# esp.net
KiCad netlist of a schematic drawn in Altium Designer
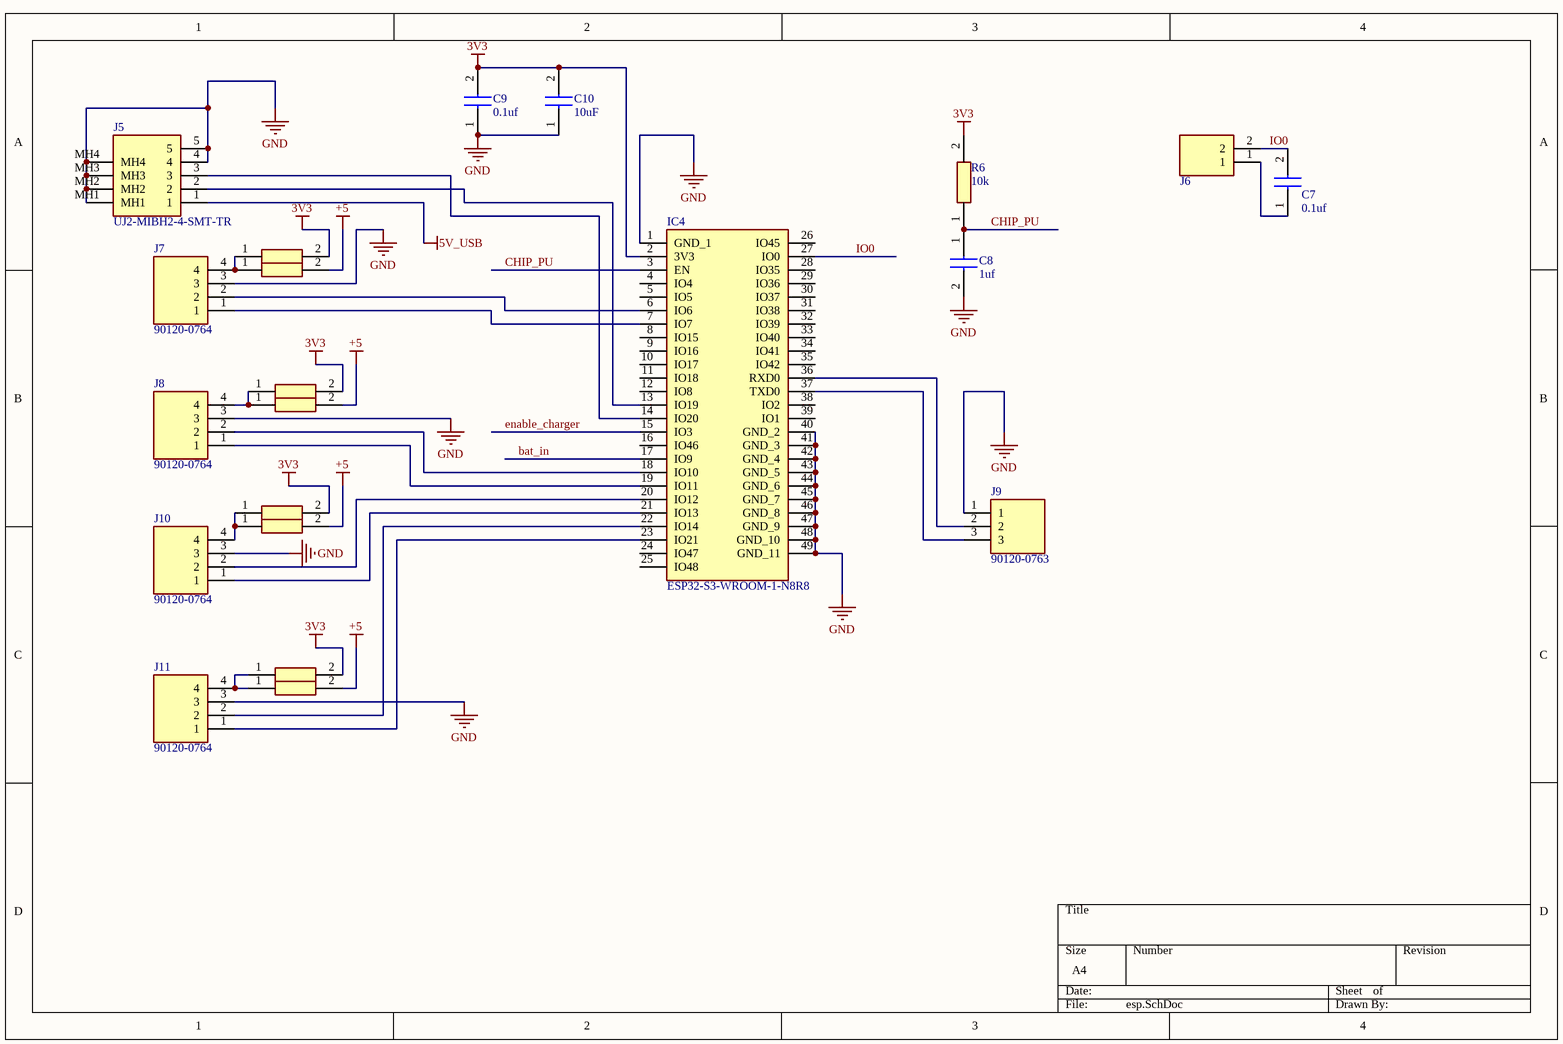
[diagram p0: esp.SchDoc]

(export (version "E")
  (design (tool "Eeschema 10.0.6"))
  (components
    (comp (ref "C7")
      (value "0.1uf")
      (footprint "SamacSys:C0805")
      (description "Capacitor")
      (fields (field (name "MANUFACTURER_PART_NUMBER") "C0805C104J5RACTM"))
      (libsource (lib "*") (part "C0805C104J5RACTM"))
    )
    (comp (ref "C8")
      (value "1uf")
      (footprint "SamacSys:C0805")
      (description "Capacitor")
      (fields (field (name "MANUFACTURER_PART_NUMBER") "C0805C104J5RACTM"))
      (libsource (lib "*") (part "C0805C104J5RACTM"))
    )
    (comp (ref "C9")
      (value "0.1uf")
      (footprint "SamacSys:CAPC2012X145N")
      (description "Capacitor")
      (fields
        (field (name "MANUFACTURER_PART_NUMBER") "VJ0805Y104KXAAT")
        (field (name "MOUSER PART NUMBER") "77-VJ0805Y104KXAAT")
      )
      (libsource (lib "*") (part "VJ0805Y104KXAAT"))
    )
    (comp (ref "C10")
      (value "10uF")
      (footprint "SamacSys:CAPC2114X145N")
      (description "Capacitor")
      (fields
        (field (name "MANUFACTURER_PART_NUMBER") "LMR212BD7106KG-T")
        (field (name "MOUSER PART NUMBER") "963-LMR212BD7106KG-T")
      )
      (libsource (lib "*") (part "LMR212BD7106KG-T"))
    )
    (comp (ref "IC4")
      (value "ESP32-S3-WROOM-1-N8R8")
      (footprint "SamacSys:ESP32S3WROOM1N8R8")
      (description "Integrated Circuit")
      (fields (field (name "MOUSER PART NUMBER") "356-EP32S3WROOM1N8R8"))
      (libsource (lib "*") (part "ESP32-S3-WROOM-1-N8R8"))
    )
    (comp (ref "J5")
      (value "UJ2-MIBH2-4-SMT-TR")
      (footprint "SamacSys:UJ2MIBH24SMTTR")
      (description "Connector")
      (fields (field (name "MOUSER PART NUMBER") "490-UJ2-MIBH2-4-SMT"))
      (libsource (lib "*") (part "UJ2-MIBH2-4-SMT-TR"))
    )
    (comp (ref "J6")
      (value "10129378-902001BLF")
      (footprint "SamacSys:HDRV2W67P0X254_1X2_508X241X843P")
      (description "Connector")
      (fields (field (name "MOUSER PART NUMBER") "649-1012937890201BLF"))
      (libsource (lib "*") (part "10129378-902001BLF"))
    )
    (comp (ref "J7")
      (value "90120-0764")
      (footprint "SamacSys:HDRV4W90P0X254_1X4_994X249X560P")
      (description "Connector")
      (fields (field (name "MOUSER PART NUMBER") "538-90120-0764"))
      (libsource (lib "SamacSys") (part "90120-0764"))
    )
    (comp (ref "J8")
      (value "90120-0764")
      (footprint "SamacSys:HDRV4W90P0X254_1X4_994X249X560P")
      (description "Connector")
      (fields (field (name "MOUSER PART NUMBER") "538-90120-0764"))
      (libsource (lib "SamacSys") (part "90120-0764"))
    )
    (comp (ref "J9")
      (value "90120-0763")
      (footprint "SamacSys:HDRV3W90P0X254_1X3_740X249X560P")
      (description "Connector")
      (fields (field (name "MOUSER PART NUMBER") "538-90120-0763"))
      (libsource (lib "*") (part "90120-0763"))
    )
    (comp (ref "J10")
      (value "90120-0764")
      (footprint "SamacSys:HDRV4W90P0X254_1X4_994X249X560P")
      (description "Connector")
      (fields (field (name "MOUSER PART NUMBER") "538-90120-0764"))
      (libsource (lib "SamacSys") (part "90120-0764"))
    )
    (comp (ref "J11")
      (value "90120-0764")
      (footprint "SamacSys:HDRV4W90P0X254_1X4_994X249X560P")
      (description "Connector")
      (fields (field (name "MOUSER PART NUMBER") "538-90120-0764"))
      (libsource (lib "SamacSys") (part "90120-0764"))
    )
    (comp (ref "R6")
      (value "10k")
      (footprint "SamacSys:RESC2012X65N")
      (description "Resistor")
      (fields
        (field (name "MANUFACTURER_PART_NUMBER") "CPF0805B10K5E1")
        (field (name "MOUSER PART NUMBER") "279-CPF0805B10K5E1")
      )
      (libsource (lib "*") (part "CPF0805B10K5E1"))
    )
    (comp (ref "R7")
      (value "CRCW08050000Z0EB")
      (footprint "SamacSys:RESC2012X50N")
      (description "Resistor")
      (fields (field (name "MOUSER PART NUMBER") "71-CRCW08050000Z0EB"))
      (libsource (lib "*") (part "CRCW08050000Z0EB"))
    )
    (comp (ref "R8")
      (value "CRCW08050000Z0EB")
      (footprint "SamacSys:RESC2012X50N")
      (description "Resistor")
      (fields (field (name "MOUSER PART NUMBER") "71-CRCW08050000Z0EB"))
      (libsource (lib "*") (part "CRCW08050000Z0EB"))
    )
    (comp (ref "R9")
      (value "CRCW08050000Z0EB")
      (footprint "SamacSys:RESC2012X50N")
      (description "Resistor")
      (fields (field (name "MOUSER PART NUMBER") "71-CRCW08050000Z0EB"))
      (libsource (lib "*") (part "CRCW08050000Z0EB"))
    )
    (comp (ref "R10")
      (value "CRCW08050000Z0EB")
      (footprint "SamacSys:RESC2012X50N")
      (description "Resistor")
      (fields (field (name "MOUSER PART NUMBER") "71-CRCW08050000Z0EB"))
      (libsource (lib "*") (part "CRCW08050000Z0EB"))
    )
    (comp (ref "R11")
      (value "CRCW08050000Z0EB")
      (footprint "SamacSys:RESC2012X50N")
      (description "Resistor")
      (fields (field (name "MOUSER PART NUMBER") "71-CRCW08050000Z0EB"))
      (libsource (lib "*") (part "CRCW08050000Z0EB"))
    )
    (comp (ref "R12")
      (value "CRCW08050000Z0EB")
      (footprint "SamacSys:RESC2012X50N")
      (description "Resistor")
      (fields (field (name "MOUSER PART NUMBER") "71-CRCW08050000Z0EB"))
      (libsource (lib "*") (part "CRCW08050000Z0EB"))
    )
    (comp (ref "R13")
      (value "CRCW08050000Z0EB")
      (footprint "SamacSys:RESC2012X50N")
      (description "Resistor")
      (fields (field (name "MOUSER PART NUMBER") "71-CRCW08050000Z0EB"))
      (libsource (lib "*") (part "CRCW08050000Z0EB"))
    )
    (comp (ref "R14")
      (value "CRCW08050000Z0EB")
      (footprint "SamacSys:RESC2012X50N")
      (description "Resistor")
      (fields (field (name "MOUSER PART NUMBER") "71-CRCW08050000Z0EB"))
      (libsource (lib "*") (part "CRCW08050000Z0EB"))
    )
  )
  (nets
    (net (code "1") (name "+5") (class "Default")
      (node (ref "R10") (pin "2") (pinfunction "2_2") (pintype "passive"))
      (node (ref "R12") (pin "2") (pinfunction "2_2") (pintype "passive"))
      (node (ref "R14") (pin "2") (pinfunction "2_2") (pintype "passive"))
      (node (ref "R8") (pin "2") (pinfunction "2_2") (pintype "passive"))
    )
    (net (code "2") (name "/CHIP_PU") (class "Default")
      (node (ref "C8") (pin "1") (pinfunction "1_1") (pintype "passive"))
      (node (ref "IC4") (pin "3") (pinfunction "EN_3") (pintype "passive"))
      (node (ref "R6") (pin "1") (pinfunction "1_1") (pintype "passive"))
    )
    (net (code "3") (name "/IO0") (class "Default")
      (node (ref "C7") (pin "2") (pinfunction "2_2") (pintype "passive"))
      (node (ref "IC4") (pin "27") (pinfunction "IO0_27") (pintype "passive"))
      (node (ref "J6") (pin "2") (pinfunction "2_2") (pintype "passive"))
    )
    (net (code "4") (name "/bat_in") (class "Default")
      (node (ref "IC4") (pin "17") (pinfunction "IO9_17") (pintype "passive"))
    )
    (net (code "5") (name "/enable_charger") (class "Default")
      (node (ref "IC4") (pin "15") (pinfunction "IO3_15") (pintype "passive"))
    )
    (net (code "6") (name "3V3") (class "Default")
      (node (ref "C10") (pin "2") (pinfunction "2_2") (pintype "passive"))
      (node (ref "C9") (pin "2") (pinfunction "2_2") (pintype "passive"))
      (node (ref "IC4") (pin "2") (pinfunction "3V3_2") (pintype "passive"))
      (node (ref "R11") (pin "2") (pinfunction "2_2") (pintype "passive"))
      (node (ref "R13") (pin "2") (pinfunction "2_2") (pintype "passive"))
      (node (ref "R6") (pin "2") (pinfunction "2_2") (pintype "passive"))
      (node (ref "R7") (pin "2") (pinfunction "2_2") (pintype "passive"))
      (node (ref "R9") (pin "2") (pinfunction "2_2") (pintype "passive"))
    )
    (net (code "7") (name "5V_USB") (class "Default")
      (node (ref "J5") (pin "1") (pinfunction "1_1") (pintype "passive"))
    )
    (net (code "8") (name "GND") (class "Default")
      (node (ref "C10") (pin "1") (pinfunction "1_1") (pintype "passive"))
      (node (ref "C8") (pin "2") (pinfunction "2_2") (pintype "passive"))
      (node (ref "C9") (pin "1") (pinfunction "1_1") (pintype "passive"))
      (node (ref "IC4") (pin "1") (pinfunction "GND_1_1") (pintype "passive"))
      (node (ref "IC4") (pin "40") (pinfunction "GND_2_40") (pintype "passive"))
      (node (ref "IC4") (pin "41") (pinfunction "GND_3_41") (pintype "passive"))
      (node (ref "IC4") (pin "42") (pinfunction "GND_4_42") (pintype "passive"))
      (node (ref "IC4") (pin "43") (pinfunction "GND_5_43") (pintype "passive"))
      (node (ref "IC4") (pin "44") (pinfunction "GND_6_44") (pintype "passive"))
      (node (ref "IC4") (pin "45") (pinfunction "GND_7_45") (pintype "passive"))
      (node (ref "IC4") (pin "46") (pinfunction "GND_8_46") (pintype "passive"))
      (node (ref "IC4") (pin "47") (pinfunction "GND_9_47") (pintype "passive"))
      (node (ref "IC4") (pin "48") (pinfunction "GND_10_48") (pintype "passive"))
      (node (ref "IC4") (pin "49") (pinfunction "GND_11_49") (pintype "passive"))
      (node (ref "J10") (pin "3") (pinfunction "3_3") (pintype "passive"))
      (node (ref "J11") (pin "3") (pinfunction "3_3") (pintype "passive"))
      (node (ref "J5") (pin "4") (pinfunction "4_4") (pintype "passive"))
      (node (ref "J5") (pin "5") (pinfunction "5_5") (pintype "passive"))
      (node (ref "J5") (pin "MH1") (pinfunction "MH1_MH1") (pintype "passive"))
      (node (ref "J5") (pin "MH2") (pinfunction "MH2_MH2") (pintype "passive"))
      (node (ref "J5") (pin "MH3") (pinfunction "MH3_MH3") (pintype "passive"))
      (node (ref "J5") (pin "MH4") (pinfunction "MH4_MH4") (pintype "passive"))
      (node (ref "J7") (pin "3") (pinfunction "3_3") (pintype "passive"))
      (node (ref "J8") (pin "3") (pinfunction "3_3") (pintype "passive"))
      (node (ref "J9") (pin "1") (pinfunction "1_1") (pintype "passive"))
    )
    (net (code "9") (name "Net-(C7-Pad1)") (class "Default")
      (node (ref "C7") (pin "1") (pinfunction "1_1") (pintype "passive"))
      (node (ref "J6") (pin "1") (pinfunction "1_1") (pintype "passive"))
    )
    (net (code "10") (name "Net-(IC4-IO6)") (class "Default")
      (node (ref "IC4") (pin "6") (pinfunction "IO6_6") (pintype "passive"))
      (node (ref "J7") (pin "2") (pinfunction "2_2") (pintype "passive"))
    )
    (net (code "11") (name "Net-(IC4-IO7)") (class "Default")
      (node (ref "IC4") (pin "7") (pinfunction "IO7_7") (pintype "passive"))
      (node (ref "J7") (pin "1") (pinfunction "1_1") (pintype "passive"))
    )
    (net (code "12") (name "Net-(IC4-IO10)") (class "Default")
      (node (ref "IC4") (pin "18") (pinfunction "IO10_18") (pintype "passive"))
      (node (ref "J8") (pin "2") (pinfunction "2_2") (pintype "passive"))
    )
    (net (code "13") (name "Net-(IC4-IO11)") (class "Default")
      (node (ref "IC4") (pin "19") (pinfunction "IO11_19") (pintype "passive"))
      (node (ref "J8") (pin "1") (pinfunction "1_1") (pintype "passive"))
    )
    (net (code "14") (name "Net-(IC4-IO12)") (class "Default")
      (node (ref "IC4") (pin "20") (pinfunction "IO12_20") (pintype "passive"))
      (node (ref "J10") (pin "2") (pinfunction "2_2") (pintype "passive"))
    )
    (net (code "15") (name "Net-(IC4-IO13)") (class "Default")
      (node (ref "IC4") (pin "21") (pinfunction "IO13_21") (pintype "passive"))
      (node (ref "J10") (pin "1") (pinfunction "1_1") (pintype "passive"))
    )
    (net (code "16") (name "Net-(IC4-IO14)") (class "Default")
      (node (ref "IC4") (pin "22") (pinfunction "IO14_22") (pintype "passive"))
      (node (ref "J11") (pin "2") (pinfunction "2_2") (pintype "passive"))
    )
    (net (code "17") (name "Net-(IC4-IO19)") (class "Default")
      (node (ref "IC4") (pin "13") (pinfunction "IO19_13") (pintype "passive"))
      (node (ref "J5") (pin "2") (pinfunction "2_2") (pintype "passive"))
    )
    (net (code "18") (name "Net-(IC4-IO20)") (class "Default")
      (node (ref "IC4") (pin "14") (pinfunction "IO20_14") (pintype "passive"))
      (node (ref "J5") (pin "3") (pinfunction "3_3") (pintype "passive"))
    )
    (net (code "19") (name "Net-(IC4-IO21)") (class "Default")
      (node (ref "IC4") (pin "23") (pinfunction "IO21_23") (pintype "passive"))
      (node (ref "J11") (pin "1") (pinfunction "1_1") (pintype "passive"))
    )
    (net (code "20") (name "Net-(IC4-RXD0)") (class "Default")
      (node (ref "IC4") (pin "36") (pinfunction "RXD0_36") (pintype "passive"))
      (node (ref "J9") (pin "2") (pinfunction "2_2") (pintype "passive"))
    )
    (net (code "21") (name "Net-(IC4-TXD0)") (class "Default")
      (node (ref "IC4") (pin "37") (pinfunction "TXD0_37") (pintype "passive"))
      (node (ref "J9") (pin "3") (pinfunction "3_3") (pintype "passive"))
    )
    (net (code "22") (name "Net-(J7-Pad4)") (class "Default")
      (node (ref "J7") (pin "4") (pinfunction "4_4") (pintype "passive"))
      (node (ref "R7") (pin "1") (pinfunction "1_1") (pintype "passive"))
      (node (ref "R8") (pin "1") (pinfunction "1_1") (pintype "passive"))
    )
    (net (code "23") (name "Net-(J8-Pad4)") (class "Default")
      (node (ref "J8") (pin "4") (pinfunction "4_4") (pintype "passive"))
      (node (ref "R10") (pin "1") (pinfunction "1_1") (pintype "passive"))
      (node (ref "R9") (pin "1") (pinfunction "1_1") (pintype "passive"))
    )
    (net (code "24") (name "Net-(J10-Pad4)") (class "Default")
      (node (ref "J10") (pin "4") (pinfunction "4_4") (pintype "passive"))
      (node (ref "R11") (pin "1") (pinfunction "1_1") (pintype "passive"))
      (node (ref "R12") (pin "1") (pinfunction "1_1") (pintype "passive"))
    )
    (net (code "25") (name "Net-(J11-Pad4)") (class "Default")
      (node (ref "J11") (pin "4") (pinfunction "4_4") (pintype "passive"))
      (node (ref "R13") (pin "1") (pinfunction "1_1") (pintype "passive"))
      (node (ref "R14") (pin "1") (pinfunction "1_1") (pintype "passive"))
    )
    (net (code "26") (name "unconnected-(IC4-IO1-Pad39)") (class "Default")
      (node (ref "IC4") (pin "39") (pinfunction "IO1_39") (pintype "passive"))
    )
    (net (code "27") (name "unconnected-(IC4-IO2-Pad38)") (class "Default")
      (node (ref "IC4") (pin "38") (pinfunction "IO2_38") (pintype "passive"))
    )
    (net (code "28") (name "unconnected-(IC4-IO4-Pad4)") (class "Default")
      (node (ref "IC4") (pin "4") (pinfunction "IO4_4") (pintype "passive"))
    )
    (net (code "29") (name "unconnected-(IC4-IO5-Pad5)") (class "Default")
      (node (ref "IC4") (pin "5") (pinfunction "IO5_5") (pintype "passive"))
    )
    (net (code "30") (name "unconnected-(IC4-IO8-Pad12)") (class "Default")
      (node (ref "IC4") (pin "12") (pinfunction "IO8_12") (pintype "passive"))
    )
    (net (code "31") (name "unconnected-(IC4-IO15-Pad8)") (class "Default")
      (node (ref "IC4") (pin "8") (pinfunction "IO15_8") (pintype "passive"))
    )
    (net (code "32") (name "unconnected-(IC4-IO16-Pad9)") (class "Default")
      (node (ref "IC4") (pin "9") (pinfunction "IO16_9") (pintype "passive"))
    )
    (net (code "33") (name "unconnected-(IC4-IO17-Pad10)") (class "Default")
      (node (ref "IC4") (pin "10") (pinfunction "IO17_10") (pintype "passive"))
    )
    (net (code "34") (name "unconnected-(IC4-IO18-Pad11)") (class "Default")
      (node (ref "IC4") (pin "11") (pinfunction "IO18_11") (pintype "passive"))
    )
    (net (code "35") (name "unconnected-(IC4-IO35-Pad28)") (class "Default")
      (node (ref "IC4") (pin "28") (pinfunction "IO35_28") (pintype "passive"))
    )
    (net (code "36") (name "unconnected-(IC4-IO36-Pad29)") (class "Default")
      (node (ref "IC4") (pin "29") (pinfunction "IO36_29") (pintype "passive"))
    )
    (net (code "37") (name "unconnected-(IC4-IO37-Pad30)") (class "Default")
      (node (ref "IC4") (pin "30") (pinfunction "IO37_30") (pintype "passive"))
    )
    (net (code "38") (name "unconnected-(IC4-IO38-Pad31)") (class "Default")
      (node (ref "IC4") (pin "31") (pinfunction "IO38_31") (pintype "passive"))
    )
    (net (code "39") (name "unconnected-(IC4-IO39-Pad32)") (class "Default")
      (node (ref "IC4") (pin "32") (pinfunction "IO39_32") (pintype "passive"))
    )
    (net (code "40") (name "unconnected-(IC4-IO40-Pad33)") (class "Default")
      (node (ref "IC4") (pin "33") (pinfunction "IO40_33") (pintype "passive"))
    )
    (net (code "41") (name "unconnected-(IC4-IO41-Pad34)") (class "Default")
      (node (ref "IC4") (pin "34") (pinfunction "IO41_34") (pintype "passive"))
    )
    (net (code "42") (name "unconnected-(IC4-IO42-Pad35)") (class "Default")
      (node (ref "IC4") (pin "35") (pinfunction "IO42_35") (pintype "passive"))
    )
    (net (code "43") (name "unconnected-(IC4-IO45-Pad26)") (class "Default")
      (node (ref "IC4") (pin "26") (pinfunction "IO45_26") (pintype "passive"))
    )
    (net (code "44") (name "unconnected-(IC4-IO46-Pad16)") (class "Default")
      (node (ref "IC4") (pin "16") (pinfunction "IO46_16") (pintype "passive"))
    )
    (net (code "45") (name "unconnected-(IC4-IO47-Pad24)") (class "Default")
      (node (ref "IC4") (pin "24") (pinfunction "IO47_24") (pintype "passive"))
    )
    (net (code "46") (name "unconnected-(IC4-IO48-Pad25)") (class "Default")
      (node (ref "IC4") (pin "25") (pinfunction "IO48_25") (pintype "passive"))
    )
  )
)
